# snowflake.net
KiCad netlist of a schematic drawn in EAGLE
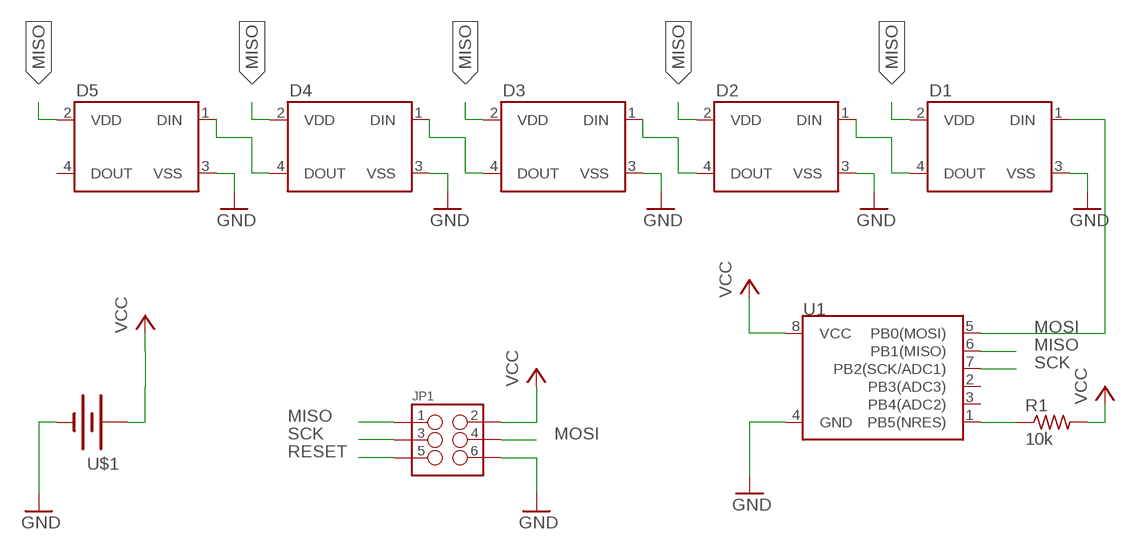
[diagram p0: schematic, sheet 1]

(export (version "E")
  (design (tool "Eeschema 10.0.6"))
  (components
    (comp (ref "D1")
      (value "WS2812BEDGE_MOUNT_5MM_LED")
      (footprint "eagle-import:WS2812B")
      (libsource (lib "eagle-import") (part "WS2812BEDGE_MOUNT_5MM_LED"))
    )
    (comp (ref "D2")
      (value "WS2812BEDGE_MOUNT_5MM_LED")
      (footprint "eagle-import:WS2812B")
      (libsource (lib "eagle-import") (part "WS2812BEDGE_MOUNT_5MM_LED"))
    )
    (comp (ref "D3")
      (value "WS2812BEDGE_MOUNT_5MM_LED")
      (footprint "eagle-import:WS2812B")
      (libsource (lib "eagle-import") (part "WS2812BEDGE_MOUNT_5MM_LED"))
    )
    (comp (ref "D4")
      (value "WS2812BEDGE_MOUNT_5MM_LED")
      (footprint "eagle-import:WS2812B")
      (libsource (lib "eagle-import") (part "WS2812BEDGE_MOUNT_5MM_LED"))
    )
    (comp (ref "D5")
      (value "WS2812BEDGE_MOUNT_5MM_LED")
      (footprint "eagle-import:WS2812B")
      (libsource (lib "eagle-import") (part "WS2812BEDGE_MOUNT_5MM_LED"))
    )
    (comp (ref "JP1")
      (value "M03X2POGO_PINS")
      (footprint "eagle-import:2X3_POGO")
      (libsource (lib "eagle-import") (part "M03X2POGO_PINS"))
    )
    (comp (ref "R1")
      (value "10k")
      (footprint "eagle-import:R0805")
      (libsource (lib "eagle-import") (part "R-US_R0805"))
    )
    (comp (ref "U$1")
      (value "BATTERY")
      (footprint "eagle-import:BHX2-2032-SM")
      (libsource (lib "eagle-import") (part "BATTERY"))
    )
    (comp (ref "U1")
      (value "ATTINY45TINY85-20-SMT")
      (footprint "eagle-import:SO08-EIAJ")
      (libsource (lib "eagle-import") (part "ATTINY45TINY85-20-SMT"))
    )
  )
  (nets
    (net (code "1") (name "/MOSI") (class "Default")
      (node (ref "D1") (pin "1") (pinfunction "DIN_1") (pintype "input"))
      (node (ref "JP1") (pin "P$4") (pinfunction "4_P$4") (pintype "bidirectional"))
      (node (ref "U1") (pin "5") (pinfunction "PB0(MOSI)_5") (pintype "bidirectional"))
    )
    (net (code "2") (name "/RESET") (class "Default")
      (node (ref "JP1") (pin "P$5") (pinfunction "5_P$5") (pintype "bidirectional"))
      (node (ref "R1") (pin "1") (pinfunction "1_1") (pintype "passive"))
      (node (ref "U1") (pin "1") (pinfunction "PB5(NRES)_1") (pintype "bidirectional"))
    )
    (net (code "3") (name "/SCK") (class "Default")
      (node (ref "JP1") (pin "P$3") (pinfunction "3_P$3") (pintype "bidirectional"))
      (node (ref "U1") (pin "7") (pinfunction "PB2(SCK/ADC1)_7") (pintype "bidirectional"))
    )
    (net (code "4") (name "GND") (class "Default")
      (node (ref "D1") (pin "3") (pinfunction "VSS_3") (pintype "power_in"))
      (node (ref "D2") (pin "3") (pinfunction "VSS_3") (pintype "power_in"))
      (node (ref "D3") (pin "3") (pinfunction "VSS_3") (pintype "power_in"))
      (node (ref "D4") (pin "3") (pinfunction "VSS_3") (pintype "power_in"))
      (node (ref "D5") (pin "3") (pinfunction "VSS_3") (pintype "power_in"))
      (node (ref "JP1") (pin "P$6") (pinfunction "6_P$6") (pintype "bidirectional"))
      (node (ref "U$1") (pin "GND") (pinfunction "-_GND") (pintype "power_in"))
      (node (ref "U1") (pin "4") (pinfunction "GND_4") (pintype "bidirectional"))
    )
    (net (code "5") (name "MISO") (class "Default")
      (node (ref "D1") (pin "2") (pinfunction "VDD_2") (pintype "power_in"))
      (node (ref "D2") (pin "2") (pinfunction "VDD_2") (pintype "power_in"))
      (node (ref "D3") (pin "2") (pinfunction "VDD_2") (pintype "power_in"))
      (node (ref "D4") (pin "2") (pinfunction "VDD_2") (pintype "power_in"))
      (node (ref "D5") (pin "2") (pinfunction "VDD_2") (pintype "power_in"))
      (node (ref "JP1") (pin "P$1") (pinfunction "1_P$1") (pintype "bidirectional"))
      (node (ref "U1") (pin "6") (pinfunction "PB1(MISO)_6") (pintype "bidirectional"))
    )
    (net (code "6") (name "Net-(D1-DOUT)") (class "Default")
      (node (ref "D1") (pin "4") (pinfunction "DOUT_4") (pintype "output"))
      (node (ref "D2") (pin "1") (pinfunction "DIN_1") (pintype "input"))
    )
    (net (code "7") (name "Net-(D2-DOUT)") (class "Default")
      (node (ref "D2") (pin "4") (pinfunction "DOUT_4") (pintype "output"))
      (node (ref "D3") (pin "1") (pinfunction "DIN_1") (pintype "input"))
    )
    (net (code "8") (name "Net-(D3-DOUT)") (class "Default")
      (node (ref "D3") (pin "4") (pinfunction "DOUT_4") (pintype "output"))
      (node (ref "D4") (pin "1") (pinfunction "DIN_1") (pintype "input"))
    )
    (net (code "9") (name "Net-(D4-DOUT)") (class "Default")
      (node (ref "D4") (pin "4") (pinfunction "DOUT_4") (pintype "output"))
      (node (ref "D5") (pin "1") (pinfunction "DIN_1") (pintype "input"))
    )
    (net (code "10") (name "VCC") (class "Default")
      (node (ref "JP1") (pin "P$2") (pinfunction "2_P$2") (pintype "bidirectional"))
      (node (ref "R1") (pin "2") (pinfunction "2_2") (pintype "passive"))
      (node (ref "U$1") (pin "VCC") (pinfunction "+_VCC") (pintype "power_in"))
      (node (ref "U$1") (pin "VCC-2") (pinfunction "+_VCC-2") (pintype "power_in"))
      (node (ref "U1") (pin "8") (pinfunction "VCC_8") (pintype "bidirectional"))
    )
    (net (code "11") (name "unconnected-(D5-DOUT-Pad4)") (class "Default")
      (node (ref "D5") (pin "4") (pinfunction "DOUT_4") (pintype "output"))
    )
    (net (code "12") (name "unconnected-(U1-PB3(ADC3)-Pad2)") (class "Default")
      (node (ref "U1") (pin "2") (pinfunction "PB3(ADC3)_2") (pintype "bidirectional"))
    )
    (net (code "13") (name "unconnected-(U1-PB4(ADC2)-Pad3)") (class "Default")
      (node (ref "U1") (pin "3") (pinfunction "PB4(ADC2)_3") (pintype "bidirectional"))
    )
  )
)
